# debug_jig.net
KiCad netlist of a schematic drawn in EasyEDA Pro
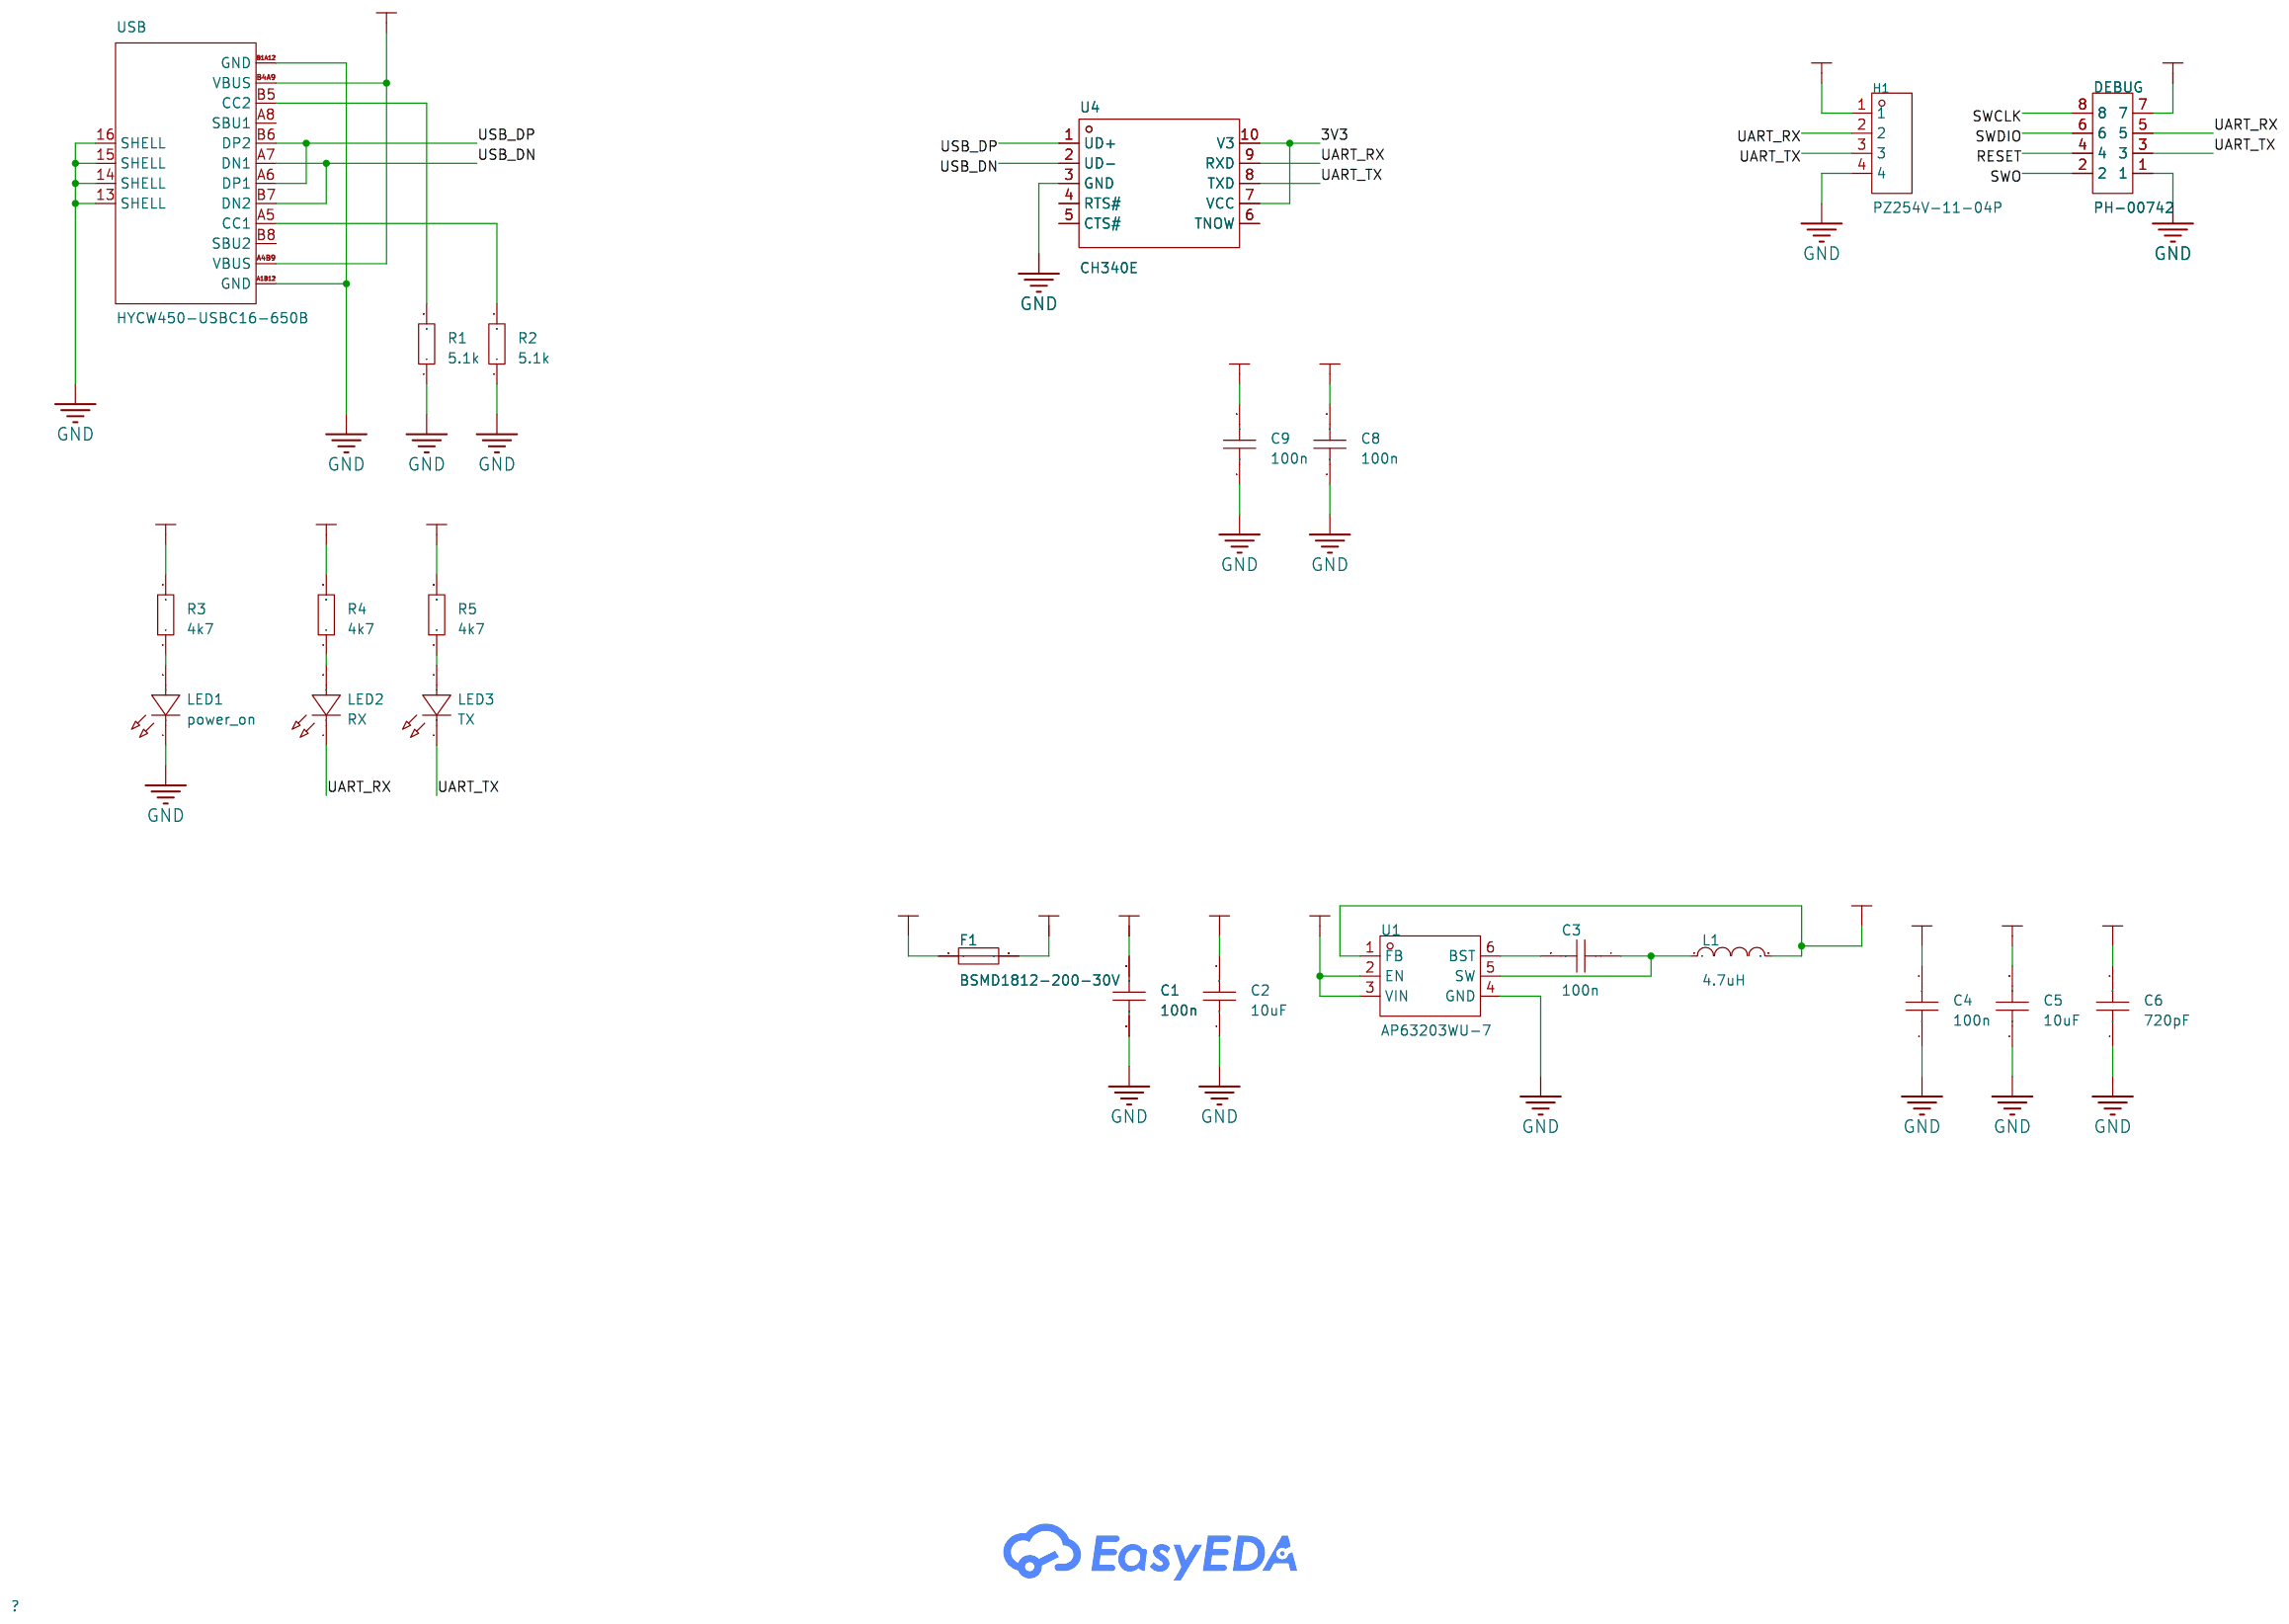
[diagram p0: schematic sheet]

(export (version "E")
  (design (tool "Eeschema 10.0.6"))
  (components
    (comp (ref "C1")
      (value "100n")
      (footprint "easyedapro:C0805")
      (description "Capacitance:10uF Tolerance:±10% Tolerance:±10% Voltage Rating:25V Temperature Coefficient:X5R")
      (fields
        (field (name "Manufacturer Part") "CL21A106KAYNNNE")
        (field (name "Manufacturer") "SAMSUNG(三星)")
      )
      (libsource (lib "easyedapro") (part "CL21A106KAYNNNE"))
    )
    (comp (ref "C2")
      (value "100n")
      (footprint "easyedapro:C0805")
      (description "Capacitance:10uF Tolerance:±10% Tolerance:±10% Voltage Rating:25V Temperature Coefficient:X5R")
      (fields
        (field (name "Manufacturer Part") "CL21A106KAYNNNE")
        (field (name "Manufacturer") "SAMSUNG(三星)")
      )
      (libsource (lib "easyedapro") (part "CL21A106KAYNNNE"))
    )
    (comp (ref "C3")
      (value "100n")
      (footprint "easyedapro:C0805")
      (description "Capacitance:10uF Tolerance:±10% Tolerance:±10% Voltage Rating:25V Temperature Coefficient:X5R")
      (fields
        (field (name "Manufacturer Part") "CL21A106KAYNNNE")
        (field (name "Manufacturer") "SAMSUNG(三星)")
      )
      (libsource (lib "easyedapro") (part "CL21A106KAYNNNE"))
    )
    (comp (ref "C4")
      (value "100n")
      (footprint "easyedapro:C0805")
      (description "Capacitance:10uF Tolerance:±10% Tolerance:±10% Voltage Rating:25V Temperature Coefficient:X5R")
      (fields
        (field (name "Manufacturer Part") "CL21A106KAYNNNE")
        (field (name "Manufacturer") "SAMSUNG(三星)")
      )
      (libsource (lib "easyedapro") (part "CL21A106KAYNNNE"))
    )
    (comp (ref "C5")
      (value "100n")
      (footprint "easyedapro:C0805")
      (description "Capacitance:10uF Tolerance:±10% Tolerance:±10% Voltage Rating:25V Temperature Coefficient:X5R")
      (fields
        (field (name "Manufacturer Part") "CL21A106KAYNNNE")
        (field (name "Manufacturer") "SAMSUNG(三星)")
      )
      (libsource (lib "easyedapro") (part "CL21A106KAYNNNE"))
    )
    (comp (ref "C6")
      (value "100n")
      (footprint "easyedapro:C0805")
      (description "Capacitance:10uF Tolerance:±10% Tolerance:±10% Voltage Rating:25V Temperature Coefficient:X5R")
      (fields
        (field (name "Manufacturer Part") "CL21A106KAYNNNE")
        (field (name "Manufacturer") "SAMSUNG(三星)")
      )
      (libsource (lib "easyedapro") (part "CL21A106KAYNNNE"))
    )
    (comp (ref "C8")
      (value "100n")
      (footprint "easyedapro:C0805")
      (description "Capacitance:10uF Tolerance:±10% Tolerance:±10% Voltage Rating:25V Temperature Coefficient:X5R")
      (fields
        (field (name "Manufacturer Part") "CL21A106KAYNNNE")
        (field (name "Manufacturer") "SAMSUNG(三星)")
      )
      (libsource (lib "easyedapro") (part "CL21A106KAYNNNE"))
    )
    (comp (ref "C9")
      (value "100n")
      (footprint "easyedapro:C0805")
      (description "Capacitance:10uF Tolerance:±10% Tolerance:±10% Voltage Rating:25V Temperature Coefficient:X5R")
      (fields
        (field (name "Manufacturer Part") "CL21A106KAYNNNE")
        (field (name "Manufacturer") "SAMSUNG(三星)")
      )
      (libsource (lib "easyedapro") (part "CL21A106KAYNNNE"))
    )
    (comp (ref "DEBUG")
      (value "PH-00742")
      (footprint "easyedapro:HDR-TH_8P-P1.27-V-M-R2-C4-S1.27")
      (fields (field (name "Manufacturer") "Liansheng(连盛)"))
      (libsource (lib "easyedapro") (part "PH-00742"))
    )
    (comp (ref "F1")
      (value "BSMD1812-200-30V")
      (footprint "easyedapro:F1812")
      (fields (field (name "Manufacturer") "BHFUSE(佰宏)"))
      (libsource (lib "easyedapro") (part "BSMD1812-200-30V"))
    )
    (comp (ref "H1")
      (value "PZ254V-11-04P")
      (footprint "easyedapro:HDR-TH_4P-P2.54-V-M")
      (fields (field (name "Manufacturer") "XFCN(兴飞)"))
      (libsource (lib "easyedapro") (part "PZ254V-11-04P_C2691448"))
    )
    (comp (ref "L1")
      (value "4.7uH")
      (footprint "easyedapro:IND-SMD_L4.0-W4.0_FNR40XXS")
      (fields (field (name "Manufacturer Part") "FNR4030S4R7MT") (field (name "Manufacturer") "cjiang(长江微电)"))
      (libsource (lib "easyedapro") (part "FNR4030S4R7MT"))
    )
    (comp (ref "LED1")
      (value "power_on")
      (footprint "easyedapro:LED1206-RD")
      (fields (field (name "Manufacturer") "YONGYUTAI(永裕泰)"))
      (libsource (lib "easyedapro") (part "YLED1206G"))
    )
    (comp (ref "LED2")
      (value "RX")
      (footprint "easyedapro:LED1206-RD")
      (fields (field (name "Manufacturer") "YONGYUTAI(永裕泰)"))
      (libsource (lib "easyedapro") (part "YLED1206G"))
    )
    (comp (ref "LED3")
      (value "TX")
      (footprint "easyedapro:LED1206-RD")
      (fields (field (name "Manufacturer") "YONGYUTAI(永裕泰)"))
      (libsource (lib "easyedapro") (part "YLED1206G"))
    )
    (comp (ref "R1")
      (value "330")
      (footprint "easyedapro:R0805")
      (fields
        (field (name "Manufacturer Part") "0805W8F1002T5E")
        (field (name "Manufacturer") "UNI-ROYAL(厚声)")
      )
      (libsource (lib "easyedapro") (part "0805W8F1002T5E"))
    )
    (comp (ref "R2")
      (value "330")
      (footprint "easyedapro:R0805")
      (fields
        (field (name "Manufacturer Part") "0805W8F1002T5E")
        (field (name "Manufacturer") "UNI-ROYAL(厚声)")
      )
      (libsource (lib "easyedapro") (part "0805W8F1002T5E"))
    )
    (comp (ref "R3")
      (value "4k7")
      (footprint "easyedapro:R0805")
      (fields
        (field (name "Manufacturer Part") "0805W8F1002T5E")
        (field (name "Manufacturer") "UNI-ROYAL(厚声)")
      )
      (libsource (lib "easyedapro") (part "0805W8F1002T5E"))
    )
    (comp (ref "R4")
      (value "4k7")
      (footprint "easyedapro:R0805")
      (fields
        (field (name "Manufacturer Part") "0805W8F1002T5E")
        (field (name "Manufacturer") "UNI-ROYAL(厚声)")
      )
      (libsource (lib "easyedapro") (part "0805W8F1002T5E"))
    )
    (comp (ref "R5")
      (value "4k7")
      (footprint "easyedapro:R0805")
      (fields
        (field (name "Manufacturer Part") "0805W8F1002T5E")
        (field (name "Manufacturer") "UNI-ROYAL(厚声)")
      )
      (libsource (lib "easyedapro") (part "0805W8F1002T5E"))
    )
    (comp (ref "U1")
      (value "AP63203WU-7")
      (footprint "easyedapro:TSOT-26_L2.9-W1.6-P0.95-LS2.8-BL")
      (fields (field (name "Manufacturer") "DIODES(美台)"))
      (libsource (lib "easyedapro") (part "AP63203WU-7"))
    )
    (comp (ref "U4")
      (value "CH340E")
      (footprint "easyedapro:MSOP-10_L3.0-W3.0-P0.50-LS5.0-BL")
      (fields (field (name "Manufacturer") "WCH(南京沁恒)"))
      (libsource (lib "easyedapro") (part "CH340E"))
    )
    (comp (ref "USB")
      (value "HYCW450-USBC16-650B")
      (footprint "easyedapro:USB-C-SMD_HYCW450-USBC16-650B")
      (fields (field (name "Manufacturer") "华宇创"))
      (libsource (lib "easyedapro") (part "HYCW450-USBC16-650B"))
    )
  )
  (nets
    (net (code "1") (name "/RESET") (class "Default")
      (node (ref "DEBUG") (pin "4") (pinfunction "4_4") (pintype "unspecified"))
    )
    (net (code "2") (name "/SWCLK") (class "Default")
      (node (ref "DEBUG") (pin "8") (pinfunction "8_8") (pintype "unspecified"))
    )
    (net (code "3") (name "/SWDIO") (class "Default")
      (node (ref "DEBUG") (pin "6") (pinfunction "6_6") (pintype "unspecified"))
    )
    (net (code "4") (name "/SWO") (class "Default")
      (node (ref "DEBUG") (pin "2") (pinfunction "2_2") (pintype "unspecified"))
    )
    (net (code "5") (name "/UART_RX") (class "Default")
      (node (ref "DEBUG") (pin "5") (pinfunction "5_5") (pintype "unspecified"))
      (node (ref "H1") (pin "2") (pinfunction "2_2") (pintype "input"))
      (node (ref "LED2") (pin "1") (pinfunction "K_1") (pintype "unspecified"))
      (node (ref "U4") (pin "9") (pinfunction "RXD_9") (pintype "unspecified"))
    )
    (net (code "6") (name "/UART_TX") (class "Default")
      (node (ref "DEBUG") (pin "3") (pinfunction "3_3") (pintype "unspecified"))
      (node (ref "H1") (pin "3") (pinfunction "3_3") (pintype "input"))
      (node (ref "LED3") (pin "1") (pinfunction "K_1") (pintype "unspecified"))
      (node (ref "U4") (pin "8") (pinfunction "TXD_8") (pintype "unspecified"))
    )
    (net (code "7") (name "/USB_DN") (class "Default")
      (node (ref "U4") (pin "2") (pinfunction "UD-_2") (pintype "unspecified"))
      (node (ref "USB") (pin "A7") (pinfunction "DN1_A7") (pintype "unspecified"))
      (node (ref "USB") (pin "B7") (pinfunction "DN2_B7") (pintype "unspecified"))
    )
    (net (code "8") (name "/USB_DP") (class "Default")
      (node (ref "U4") (pin "1") (pinfunction "UD+_1") (pintype "unspecified"))
      (node (ref "USB") (pin "A6") (pinfunction "DP1_A6") (pintype "unspecified"))
      (node (ref "USB") (pin "B6") (pinfunction "DP2_B6") (pintype "unspecified"))
    )
    (net (code "9") (name "3V3") (class "Default")
      (node (ref "C4") (pin "2") (pinfunction "2_2") (pintype "unspecified"))
      (node (ref "C5") (pin "2") (pinfunction "2_2") (pintype "unspecified"))
      (node (ref "C6") (pin "2") (pinfunction "2_2") (pintype "unspecified"))
      (node (ref "C8") (pin "2") (pinfunction "2_2") (pintype "unspecified"))
      (node (ref "C9") (pin "2") (pinfunction "2_2") (pintype "unspecified"))
      (node (ref "DEBUG") (pin "7") (pinfunction "7_7") (pintype "unspecified"))
      (node (ref "H1") (pin "1") (pinfunction "1_1") (pintype "input"))
      (node (ref "L1") (pin "2") (pinfunction "2_2") (pintype "unspecified"))
      (node (ref "R3") (pin "2") (pinfunction "2_2") (pintype "input"))
      (node (ref "R4") (pin "2") (pinfunction "2_2") (pintype "input"))
      (node (ref "R5") (pin "2") (pinfunction "2_2") (pintype "input"))
      (node (ref "U1") (pin "1") (pinfunction "FB_1") (pintype "unspecified"))
      (node (ref "U4") (pin "10") (pinfunction "V3_10") (pintype "unspecified"))
      (node (ref "U4") (pin "7") (pinfunction "VCC_7") (pintype "unspecified"))
    )
    (net (code "10") (name "5V") (class "Default")
      (node (ref "C1") (pin "2") (pinfunction "2_2") (pintype "unspecified"))
      (node (ref "C2") (pin "2") (pinfunction "2_2") (pintype "unspecified"))
      (node (ref "F1") (pin "2") (pinfunction "2_2") (pintype "unspecified"))
      (node (ref "U1") (pin "2") (pinfunction "EN_2") (pintype "unspecified"))
      (node (ref "U1") (pin "3") (pinfunction "VIN_3") (pintype "unspecified"))
    )
    (net (code "11") (name "GND") (class "Default")
      (node (ref "C1") (pin "1") (pinfunction "1_1") (pintype "unspecified"))
      (node (ref "C2") (pin "1") (pinfunction "1_1") (pintype "unspecified"))
      (node (ref "C4") (pin "1") (pinfunction "1_1") (pintype "unspecified"))
      (node (ref "C5") (pin "1") (pinfunction "1_1") (pintype "unspecified"))
      (node (ref "C6") (pin "1") (pinfunction "1_1") (pintype "unspecified"))
      (node (ref "C8") (pin "1") (pinfunction "1_1") (pintype "unspecified"))
      (node (ref "C9") (pin "1") (pinfunction "1_1") (pintype "unspecified"))
      (node (ref "DEBUG") (pin "1") (pinfunction "1_1") (pintype "unspecified"))
      (node (ref "H1") (pin "4") (pinfunction "4_4") (pintype "input"))
      (node (ref "LED1") (pin "1") (pinfunction "K_1") (pintype "unspecified"))
      (node (ref "R1") (pin "1") (pinfunction "1_1") (pintype "input"))
      (node (ref "R2") (pin "1") (pinfunction "1_1") (pintype "input"))
      (node (ref "U1") (pin "4") (pinfunction "GND_4") (pintype "unspecified"))
      (node (ref "U4") (pin "3") (pinfunction "GND_3") (pintype "unspecified"))
      (node (ref "USB") (pin "13") (pinfunction "SHELL_13") (pintype "unspecified"))
      (node (ref "USB") (pin "14") (pinfunction "SHELL_14") (pintype "unspecified"))
      (node (ref "USB") (pin "15") (pinfunction "SHELL_15") (pintype "unspecified"))
      (node (ref "USB") (pin "16") (pinfunction "SHELL_16") (pintype "unspecified"))
      (node (ref "USB") (pin "A1B12") (pinfunction "GND_A1B12") (pintype "unspecified"))
      (node (ref "USB") (pin "B1A12") (pinfunction "GND_B1A12") (pintype "unspecified"))
    )
    (net (code "12") (name "Net-(LED1-A)") (class "Default")
      (node (ref "LED1") (pin "2") (pinfunction "A_2") (pintype "unspecified"))
      (node (ref "R3") (pin "1") (pinfunction "1_1") (pintype "input"))
    )
    (net (code "13") (name "Net-(LED2-A)") (class "Default")
      (node (ref "LED2") (pin "2") (pinfunction "A_2") (pintype "unspecified"))
      (node (ref "R4") (pin "1") (pinfunction "1_1") (pintype "input"))
    )
    (net (code "14") (name "Net-(LED3-A)") (class "Default")
      (node (ref "LED3") (pin "2") (pinfunction "A_2") (pintype "unspecified"))
      (node (ref "R5") (pin "1") (pinfunction "1_1") (pintype "input"))
    )
    (net (code "15") (name "Net-(U1-BST)") (class "Default")
      (node (ref "C3") (pin "2") (pinfunction "2_2") (pintype "unspecified"))
      (node (ref "U1") (pin "6") (pinfunction "BST_6") (pintype "unspecified"))
    )
    (net (code "16") (name "Net-(U1-SW)") (class "Default")
      (node (ref "C3") (pin "1") (pinfunction "1_1") (pintype "unspecified"))
      (node (ref "L1") (pin "1") (pinfunction "1_1") (pintype "unspecified"))
      (node (ref "U1") (pin "5") (pinfunction "SW_5") (pintype "unspecified"))
    )
    (net (code "17") (name "Net-(USB-CC1)") (class "Default")
      (node (ref "R2") (pin "2") (pinfunction "2_2") (pintype "input"))
      (node (ref "USB") (pin "A5") (pinfunction "CC1_A5") (pintype "unspecified"))
    )
    (net (code "18") (name "Net-(USB-CC2)") (class "Default")
      (node (ref "R1") (pin "2") (pinfunction "2_2") (pintype "input"))
      (node (ref "USB") (pin "B5") (pinfunction "CC2_B5") (pintype "unspecified"))
    )
    (net (code "19") (name "VDD") (class "Default")
      (node (ref "F1") (pin "1") (pinfunction "1_1") (pintype "unspecified"))
      (node (ref "USB") (pin "A4B9") (pinfunction "VBUS_A4B9") (pintype "unspecified"))
      (node (ref "USB") (pin "B4A9") (pinfunction "VBUS_B4A9") (pintype "unspecified"))
    )
    (net (code "20") (name "unconnected-(U4-CTS#-Pad5)") (class "Default")
      (node (ref "U4") (pin "5") (pinfunction "CTS#_5") (pintype "unspecified"))
    )
    (net (code "21") (name "unconnected-(U4-RTS#-Pad4)") (class "Default")
      (node (ref "U4") (pin "4") (pinfunction "RTS#_4") (pintype "unspecified"))
    )
    (net (code "22") (name "unconnected-(U4-TNOW-Pad6)") (class "Default")
      (node (ref "U4") (pin "6") (pinfunction "TNOW_6") (pintype "unspecified"))
    )
    (net (code "23") (name "unconnected-(USB-SBU1-PadA8)") (class "Default")
      (node (ref "USB") (pin "A8") (pinfunction "SBU1_A8") (pintype "unspecified"))
    )
    (net (code "24") (name "unconnected-(USB-SBU2-PadB8)") (class "Default")
      (node (ref "USB") (pin "B8") (pinfunction "SBU2_B8") (pintype "unspecified"))
    )
  )
)
